# -_AI.net
KiCad netlist of a schematic drawn in EasyEDA Pro
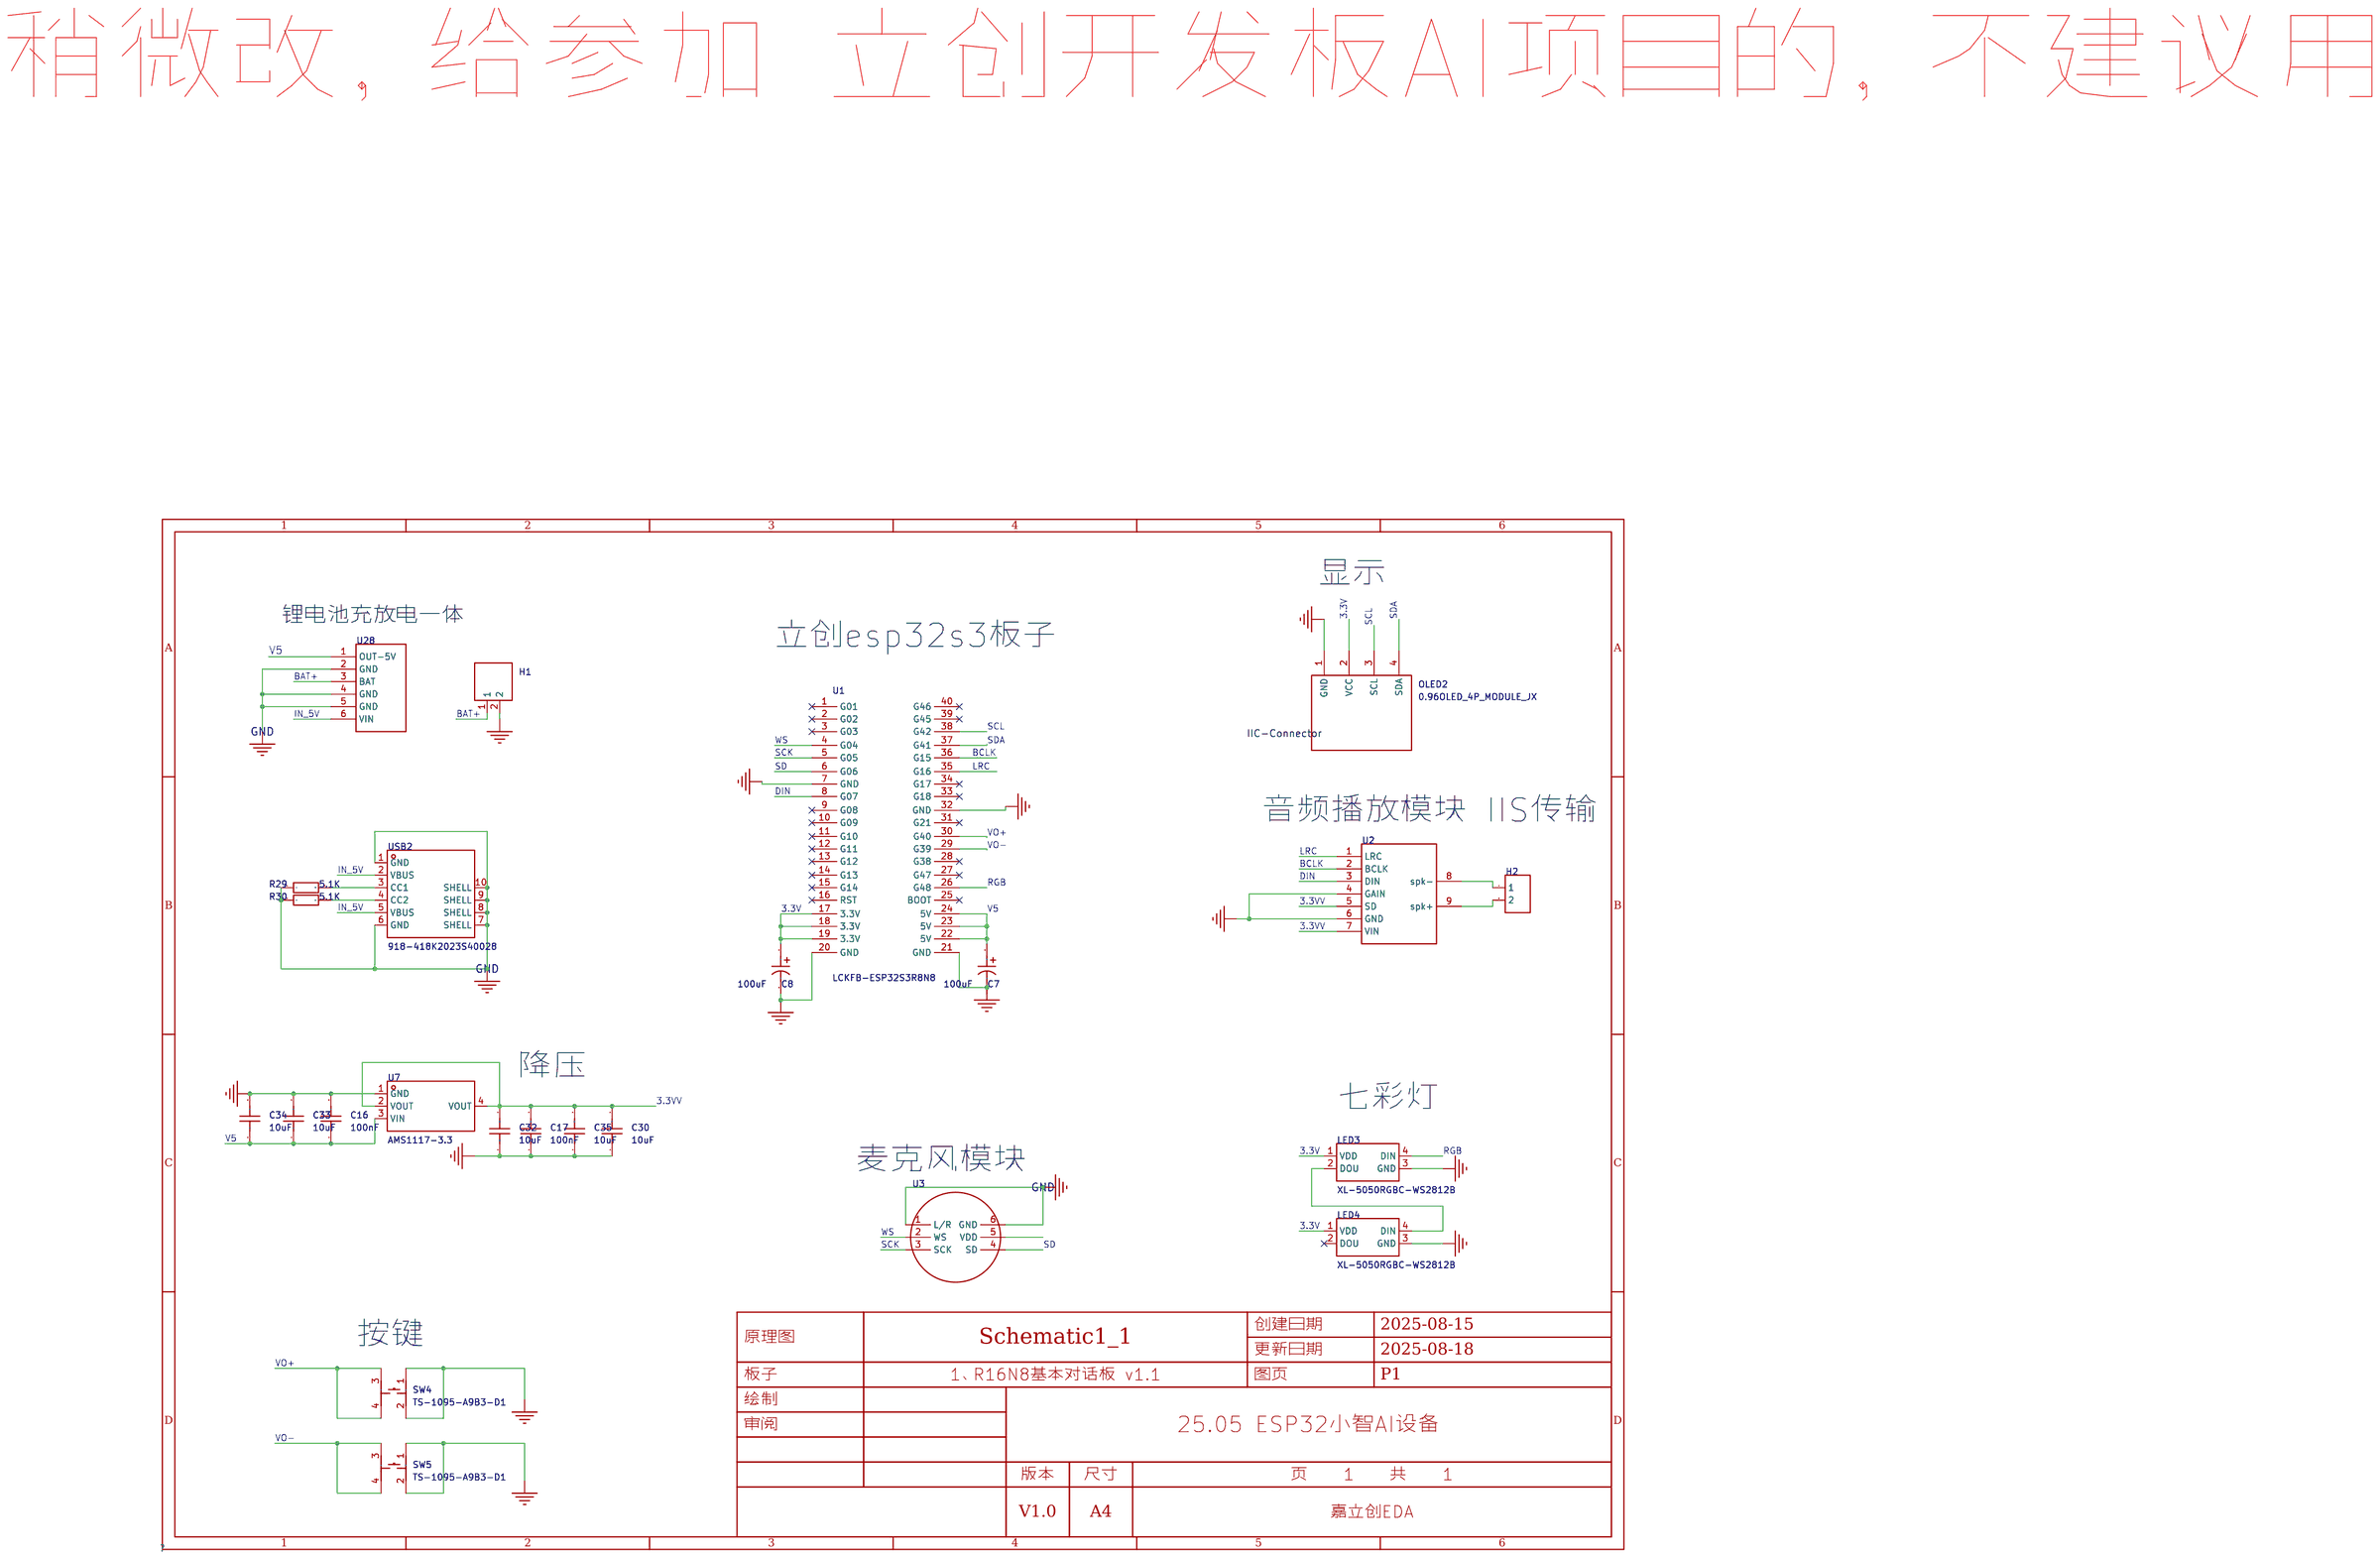
[diagram p0: schematic sheet]

(export (version "E")
  (design (tool "Eeschema 10.0.6"))
  (components
    (comp (ref "C7")
      (value "100uF")
      (footprint "easyedapro:CAP-SMD_BD6.3-L6.6-W6.6-LS7.6-RD")
      (fields (field (name "Manufacturer Part") "RVT1H101M0607") (field (name "Manufacturer") "ROQANG(容强)"))
      (libsource (lib "easyedapro") (part "RVT1H101M0607"))
    )
    (comp (ref "C8")
      (value "100uF")
      (footprint "easyedapro:CAP-SMD_BD6.3-L6.6-W6.6-LS7.6-RD")
      (fields (field (name "Manufacturer Part") "RVT1H101M0607") (field (name "Manufacturer") "ROQANG(容强)"))
      (libsource (lib "easyedapro") (part "RVT1H101M0607"))
    )
    (comp (ref "C16")
      (value "100nF")
      (footprint "easyedapro:C0603")
      (libsource (lib "easyedapro") (part "CapAcitance"))
    )
    (comp (ref "C17")
      (value "100nF")
      (footprint "easyedapro:C0603")
      (libsource (lib "easyedapro") (part "CapAcitance"))
    )
    (comp (ref "C30")
      (value "10uF")
      (footprint "easyedapro:C0603")
      (libsource (lib "easyedapro") (part "CapAcitance"))
    )
    (comp (ref "C32")
      (value "10uF")
      (footprint "easyedapro:C0603")
      (libsource (lib "easyedapro") (part "CapAcitance"))
    )
    (comp (ref "C33")
      (value "10uF")
      (footprint "easyedapro:C0603")
      (libsource (lib "easyedapro") (part "CapAcitance"))
    )
    (comp (ref "C34")
      (value "10uF")
      (footprint "easyedapro:C0603")
      (libsource (lib "easyedapro") (part "CapAcitance"))
    )
    (comp (ref "C35")
      (value "10uF")
      (footprint "easyedapro:C0603")
      (libsource (lib "easyedapro") (part "CapAcitance"))
    )
    (comp (ref "H1")
      (value "B-2100S02P-A110")
      (footprint "easyedapro:HDR-TH_2P-P2.54-V-M-1")
      (fields (field (name "Manufacturer") "Ckmtw(灿科盟)"))
      (libsource (lib "easyedapro") (part "210S-1*2P L=11.6MMGold-plated black"))
    )
    (comp (ref "H2")
      (value "~")
      (footprint "easyedapro:HDR-TH_2P-P2.54-V-F")
      (libsource (lib "easyedapro") (part "Header-Female-2.54_1x2"))
    )
    (comp (ref "LED3")
      (value "XL-5050RGBC-WS2812B")
      (footprint "easyedapro:LED-SMD_4P-L5.0-W5.0-BL_XL-5050RGBC")
      (fields (field (name "Manufacturer") "XINGLIGHT(成兴光)"))
      (libsource (lib "easyedapro") (part "XL-5050RGBC-WS2812B"))
    )
    (comp (ref "LED4")
      (value "XL-5050RGBC-WS2812B")
      (footprint "easyedapro:LED-SMD_4P-L5.0-W5.0-BL_XL-5050RGBC")
      (fields (field (name "Manufacturer") "XINGLIGHT(成兴光)"))
      (libsource (lib "easyedapro") (part "XL-5050RGBC-WS2812B"))
    )
    (comp (ref "OLED2")
      (value "0.96OLED_4P_MODULE_JX")
      (footprint "easyedapro:0.96OLED_4P")
      (libsource (lib "easyedapro") (part "0.96OLED_4P_MODULE_JX"))
    )
    (comp (ref "R29")
      (value "5.1K")
      (footprint "easyedapro:R0603")
      (libsource (lib "easyedapro") (part "电阻"))
    )
    (comp (ref "R30")
      (value "5.1K")
      (footprint "easyedapro:R0603")
      (libsource (lib "easyedapro") (part "电阻"))
    )
    (comp (ref "SW4")
      (value "TS-1095-A9B3-D1")
      (footprint "easyedapro:SW-TH_4P-L6.0-W6.0-P4.50-LS6.5")
      (fields (field (name "Manufacturer") "Yuandi(元迪)"))
      (libsource (lib "easyedapro") (part "TS-1095-A9B3-D1"))
    )
    (comp (ref "SW5")
      (value "TS-1095-A9B3-D1")
      (footprint "easyedapro:SW-TH_4P-L6.0-W6.0-P4.50-LS6.5")
      (fields (field (name "Manufacturer") "Yuandi(元迪)"))
      (libsource (lib "easyedapro") (part "TS-1095-A9B3-D1"))
    )
    (comp (ref "U1")
      (value "LCKFB-ESP32S3R8N8")
      (footprint "easyedapro:DIP-40_L20.32-W51.66-P2.54-LS15.24")
      (fields (field (name "Manufacturer") "立创开发板"))
      (libsource (lib "easyedapro") (part "LCKFB-ESP32S3R8N8"))
    )
    (comp (ref "U2") (value "~") (libsource (lib "easyedapro") (part "MAX98357A")))
    (comp (ref "U3") (value "~") (libsource (lib "easyedapro") (part "INMP441")))
    (comp (ref "U7")
      (value "AMS1117-3.3")
      (footprint "easyedapro:SOT-223-3_L6.5-W3.4-P2.30-LS7.0-BR")
      (fields (field (name "Manufacturer") "AMS"))
      (libsource (lib "easyedapro") (part "AMS1117-3.3"))
    )
    (comp (ref "U28")
      (value "~")
      (footprint "easyedapro:MH-CD42_Module")
      (libsource (lib "easyedapro") (part "mh-cd42"))
    )
    (comp (ref "USB2")
      (value "918-418K2023S40028")
      (footprint "easyedapro:USB-C-SMD_918-418K2023S40026")
      (fields (field (name "Manufacturer") "精拓金"))
      (libsource (lib "easyedapro") (part "918-418K2023S40028"))
    )
  )
  (nets
    (net (code "1") (name "/3.3V") (class "Default")
      (node (ref "C8") (pin "1") (pinfunction "1_1") (pintype "input"))
      (node (ref "LED3") (pin "1") (pinfunction "VDD_1") (pintype "unspecified"))
      (node (ref "LED4") (pin "1") (pinfunction "VDD_1") (pintype "unspecified"))
      (node (ref "OLED2") (pin "2") (pinfunction "VCC_2") (pintype "unspecified"))
      (node (ref "U1") (pin "17") (pinfunction "3.3V_17") (pintype "unspecified"))
      (node (ref "U1") (pin "18") (pinfunction "3.3V_18") (pintype "unspecified"))
      (node (ref "U1") (pin "19") (pinfunction "3.3V_19") (pintype "unspecified"))
    )
    (net (code "2") (name "/3.3VV") (class "Default")
      (node (ref "C17") (pin "2") (pinfunction "2_2") (pintype "input"))
      (node (ref "C30") (pin "2") (pinfunction "2_2") (pintype "input"))
      (node (ref "C32") (pin "2") (pinfunction "2_2") (pintype "input"))
      (node (ref "C35") (pin "2") (pinfunction "2_2") (pintype "input"))
      (node (ref "U2") (pin "5") (pinfunction "SD_5") (pintype "input"))
      (node (ref "U2") (pin "7") (pinfunction "VIN_7") (pintype "input"))
      (node (ref "U7") (pin "2") (pinfunction "VOUT_2") (pintype "unspecified"))
      (node (ref "U7") (pin "4") (pinfunction "VOUT_4") (pintype "unspecified"))
    )
    (net (code "3") (name "/BAT+") (class "Default")
      (node (ref "H1") (pin "1") (pinfunction "1_1") (pintype "unspecified"))
      (node (ref "U28") (pin "3") (pinfunction "BAT_3") (pintype "input"))
    )
    (net (code "4") (name "/BCLK") (class "Default")
      (node (ref "U1") (pin "36") (pinfunction "G15_36") (pintype "unspecified"))
      (node (ref "U2") (pin "2") (pinfunction "BCLK_2") (pintype "input"))
    )
    (net (code "5") (name "/DIN") (class "Default")
      (node (ref "U1") (pin "8") (pinfunction "G07_8") (pintype "unspecified"))
      (node (ref "U2") (pin "3") (pinfunction "DIN_3") (pintype "input"))
    )
    (net (code "6") (name "/IN_5V") (class "Default")
      (node (ref "U28") (pin "6") (pinfunction "VIN_6") (pintype "input"))
      (node (ref "USB2") (pin "2") (pinfunction "VBUS_2") (pintype "unspecified"))
      (node (ref "USB2") (pin "5") (pinfunction "VBUS_5") (pintype "unspecified"))
    )
    (net (code "7") (name "/LRC") (class "Default")
      (node (ref "U1") (pin "35") (pinfunction "G16_35") (pintype "unspecified"))
      (node (ref "U2") (pin "1") (pinfunction "LRC_1") (pintype "input"))
    )
    (net (code "8") (name "/RGB") (class "Default")
      (node (ref "LED3") (pin "4") (pinfunction "DIN_4") (pintype "unspecified"))
      (node (ref "U1") (pin "26") (pinfunction "G48_26") (pintype "unspecified"))
    )
    (net (code "9") (name "/SCK") (class "Default")
      (node (ref "U1") (pin "5") (pinfunction "G05_5") (pintype "unspecified"))
      (node (ref "U3") (pin "3") (pinfunction "SCK_3") (pintype "input"))
    )
    (net (code "10") (name "/SCL") (class "Default")
      (node (ref "OLED2") (pin "3") (pinfunction "SCL_3") (pintype "unspecified"))
      (node (ref "U1") (pin "38") (pinfunction "G42_38") (pintype "unspecified"))
    )
    (net (code "11") (name "/SD") (class "Default")
      (node (ref "U1") (pin "6") (pinfunction "G06_6") (pintype "unspecified"))
      (node (ref "U3") (pin "4") (pinfunction "SD_4") (pintype "input"))
    )
    (net (code "12") (name "/SDA") (class "Default")
      (node (ref "OLED2") (pin "4") (pinfunction "SDA_4") (pintype "unspecified"))
      (node (ref "U1") (pin "37") (pinfunction "G41_37") (pintype "unspecified"))
    )
    (net (code "13") (name "/V5") (class "Default")
      (node (ref "C16") (pin "1") (pinfunction "1_1") (pintype "input"))
      (node (ref "C33") (pin "1") (pinfunction "1_1") (pintype "input"))
      (node (ref "C34") (pin "1") (pinfunction "1_1") (pintype "input"))
      (node (ref "C7") (pin "1") (pinfunction "1_1") (pintype "input"))
      (node (ref "U1") (pin "22") (pinfunction "5V_22") (pintype "unspecified"))
      (node (ref "U1") (pin "23") (pinfunction "5V_23") (pintype "unspecified"))
      (node (ref "U1") (pin "24") (pinfunction "5V_24") (pintype "unspecified"))
      (node (ref "U28") (pin "1") (pinfunction "OUT-5V_1") (pintype "output"))
      (node (ref "U7") (pin "3") (pinfunction "VIN_3") (pintype "unspecified"))
    )
    (net (code "14") (name "/VO+") (class "Default")
      (node (ref "SW4") (pin "3") (pinfunction "3_3") (pintype "unspecified"))
      (node (ref "SW4") (pin "4") (pinfunction "4_4") (pintype "unspecified"))
      (node (ref "U1") (pin "30") (pinfunction "G40_30") (pintype "unspecified"))
    )
    (net (code "15") (name "/VO-") (class "Default")
      (node (ref "SW5") (pin "3") (pinfunction "3_3") (pintype "unspecified"))
      (node (ref "SW5") (pin "4") (pinfunction "4_4") (pintype "unspecified"))
      (node (ref "U1") (pin "29") (pinfunction "G39_29") (pintype "unspecified"))
    )
    (net (code "16") (name "/WS") (class "Default")
      (node (ref "U1") (pin "4") (pinfunction "G04_4") (pintype "unspecified"))
      (node (ref "U3") (pin "2") (pinfunction "WS_2") (pintype "input"))
    )
    (net (code "17") (name "GND") (class "Default")
      (node (ref "C16") (pin "2") (pinfunction "2_2") (pintype "input"))
      (node (ref "C17") (pin "1") (pinfunction "1_1") (pintype "input"))
      (node (ref "C30") (pin "1") (pinfunction "1_1") (pintype "input"))
      (node (ref "C32") (pin "1") (pinfunction "1_1") (pintype "input"))
      (node (ref "C33") (pin "2") (pinfunction "2_2") (pintype "input"))
      (node (ref "C34") (pin "2") (pinfunction "2_2") (pintype "input"))
      (node (ref "C35") (pin "1") (pinfunction "1_1") (pintype "input"))
      (node (ref "C7") (pin "2") (pinfunction "2_2") (pintype "input"))
      (node (ref "C8") (pin "2") (pinfunction "2_2") (pintype "input"))
      (node (ref "H1") (pin "2") (pinfunction "2_2") (pintype "unspecified"))
      (node (ref "LED3") (pin "3") (pinfunction "GND_3") (pintype "unspecified"))
      (node (ref "LED4") (pin "3") (pinfunction "GND_3") (pintype "unspecified"))
      (node (ref "OLED2") (pin "1") (pinfunction "GND_1") (pintype "unspecified"))
      (node (ref "R29") (pin "1") (pinfunction "1_1") (pintype "input"))
      (node (ref "R30") (pin "1") (pinfunction "1_1") (pintype "input"))
      (node (ref "SW4") (pin "1") (pinfunction "1_1") (pintype "unspecified"))
      (node (ref "SW4") (pin "2") (pinfunction "2_2") (pintype "unspecified"))
      (node (ref "SW5") (pin "1") (pinfunction "1_1") (pintype "unspecified"))
      (node (ref "SW5") (pin "2") (pinfunction "2_2") (pintype "unspecified"))
      (node (ref "U1") (pin "20") (pinfunction "GND_20") (pintype "unspecified"))
      (node (ref "U1") (pin "21") (pinfunction "GND_21") (pintype "unspecified"))
      (node (ref "U1") (pin "32") (pinfunction "GND_32") (pintype "unspecified"))
      (node (ref "U1") (pin "7") (pinfunction "GND_7") (pintype "unspecified"))
      (node (ref "U2") (pin "4") (pinfunction "GAIN_4") (pintype "input"))
      (node (ref "U2") (pin "6") (pinfunction "GND_6") (pintype "input"))
      (node (ref "U28") (pin "2") (pinfunction "GND_2") (pintype "input"))
      (node (ref "U28") (pin "4") (pinfunction "GND_4") (pintype "input"))
      (node (ref "U28") (pin "5") (pinfunction "GND_5") (pintype "input"))
      (node (ref "U3") (pin "1") (pinfunction "L/R_1") (pintype "input"))
      (node (ref "U3") (pin "6") (pinfunction "GND_6") (pintype "input"))
      (node (ref "U7") (pin "1") (pinfunction "GND_1") (pintype "unspecified"))
      (node (ref "USB2") (pin "1") (pinfunction "GND_1") (pintype "unspecified"))
      (node (ref "USB2") (pin "10") (pinfunction "SHELL_10") (pintype "unspecified"))
      (node (ref "USB2") (pin "6") (pinfunction "GND_6") (pintype "unspecified"))
      (node (ref "USB2") (pin "7") (pinfunction "SHELL_7") (pintype "unspecified"))
      (node (ref "USB2") (pin "8") (pinfunction "SHELL_8") (pintype "unspecified"))
      (node (ref "USB2") (pin "9") (pinfunction "SHELL_9") (pintype "unspecified"))
    )
    (net (code "18") (name "Net-(LED3-DOU)") (class "Default")
      (node (ref "LED3") (pin "2") (pinfunction "DOU_2") (pintype "unspecified"))
      (node (ref "LED4") (pin "4") (pinfunction "DIN_4") (pintype "unspecified"))
    )
    (net (code "19") (name "Net-(U2-spk+)") (class "Default")
      (node (ref "H2") (pin "2") (pinfunction "2_2") (pintype "input"))
      (node (ref "U2") (pin "9") (pinfunction "spk+_9") (pintype "input"))
    )
    (net (code "20") (name "Net-(U2-spk-)") (class "Default")
      (node (ref "H2") (pin "1") (pinfunction "1_1") (pintype "input"))
      (node (ref "U2") (pin "8") (pinfunction "spk-_8") (pintype "input"))
    )
    (net (code "21") (name "Net-(USB2-CC1)") (class "Default")
      (node (ref "R29") (pin "2") (pinfunction "2_2") (pintype "input"))
      (node (ref "USB2") (pin "3") (pinfunction "CC1_3") (pintype "unspecified"))
    )
    (net (code "22") (name "Net-(USB2-CC2)") (class "Default")
      (node (ref "R30") (pin "2") (pinfunction "2_2") (pintype "input"))
      (node (ref "USB2") (pin "4") (pinfunction "CC2_4") (pintype "unspecified"))
    )
    (net (code "23") (name "unconnected-(LED4-DOU-Pad2)") (class "Default")
      (node (ref "LED4") (pin "2") (pinfunction "DOU_2") (pintype "unspecified+no_connect"))
    )
    (net (code "24") (name "unconnected-(U1-BOOT-Pad25)") (class "Default")
      (node (ref "U1") (pin "25") (pinfunction "BOOT_25") (pintype "unspecified+no_connect"))
    )
    (net (code "25") (name "unconnected-(U1-G01-Pad1)") (class "Default")
      (node (ref "U1") (pin "1") (pinfunction "G01_1") (pintype "unspecified+no_connect"))
    )
    (net (code "26") (name "unconnected-(U1-G02-Pad2)") (class "Default")
      (node (ref "U1") (pin "2") (pinfunction "G02_2") (pintype "unspecified+no_connect"))
    )
    (net (code "27") (name "unconnected-(U1-G03-Pad3)") (class "Default")
      (node (ref "U1") (pin "3") (pinfunction "G03_3") (pintype "unspecified+no_connect"))
    )
    (net (code "28") (name "unconnected-(U1-G08-Pad9)") (class "Default")
      (node (ref "U1") (pin "9") (pinfunction "G08_9") (pintype "unspecified+no_connect"))
    )
    (net (code "29") (name "unconnected-(U1-G09-Pad10)") (class "Default")
      (node (ref "U1") (pin "10") (pinfunction "G09_10") (pintype "unspecified+no_connect"))
    )
    (net (code "30") (name "unconnected-(U1-G10-Pad11)") (class "Default")
      (node (ref "U1") (pin "11") (pinfunction "G10_11") (pintype "unspecified+no_connect"))
    )
    (net (code "31") (name "unconnected-(U1-G11-Pad12)") (class "Default")
      (node (ref "U1") (pin "12") (pinfunction "G11_12") (pintype "unspecified+no_connect"))
    )
    (net (code "32") (name "unconnected-(U1-G12-Pad13)") (class "Default")
      (node (ref "U1") (pin "13") (pinfunction "G12_13") (pintype "unspecified+no_connect"))
    )
    (net (code "33") (name "unconnected-(U1-G13-Pad14)") (class "Default")
      (node (ref "U1") (pin "14") (pinfunction "G13_14") (pintype "unspecified+no_connect"))
    )
    (net (code "34") (name "unconnected-(U1-G14-Pad15)") (class "Default")
      (node (ref "U1") (pin "15") (pinfunction "G14_15") (pintype "unspecified+no_connect"))
    )
    (net (code "35") (name "unconnected-(U1-G17-Pad34)") (class "Default")
      (node (ref "U1") (pin "34") (pinfunction "G17_34") (pintype "unspecified+no_connect"))
    )
    (net (code "36") (name "unconnected-(U1-G18-Pad33)") (class "Default")
      (node (ref "U1") (pin "33") (pinfunction "G18_33") (pintype "unspecified+no_connect"))
    )
    (net (code "37") (name "unconnected-(U1-G21-Pad31)") (class "Default")
      (node (ref "U1") (pin "31") (pinfunction "G21_31") (pintype "unspecified+no_connect"))
    )
    (net (code "38") (name "unconnected-(U1-G38-Pad28)") (class "Default")
      (node (ref "U1") (pin "28") (pinfunction "G38_28") (pintype "unspecified+no_connect"))
    )
    (net (code "39") (name "unconnected-(U1-G45-Pad39)") (class "Default")
      (node (ref "U1") (pin "39") (pinfunction "G45_39") (pintype "unspecified+no_connect"))
    )
    (net (code "40") (name "unconnected-(U1-G46-Pad40)") (class "Default")
      (node (ref "U1") (pin "40") (pinfunction "G46_40") (pintype "unspecified+no_connect"))
    )
    (net (code "41") (name "unconnected-(U1-G47-Pad27)") (class "Default")
      (node (ref "U1") (pin "27") (pinfunction "G47_27") (pintype "unspecified+no_connect"))
    )
    (net (code "42") (name "unconnected-(U1-RST-Pad16)") (class "Default")
      (node (ref "U1") (pin "16") (pinfunction "RST_16") (pintype "unspecified+no_connect"))
    )
    (net (code "43") (name "unconnected-(U3-VDD-Pad5)") (class "Default")
      (node (ref "U3") (pin "5") (pinfunction "VDD_5") (pintype "input"))
    )
  )
)
